# CAN.net
KiCad netlist of a schematic drawn in EAGLE
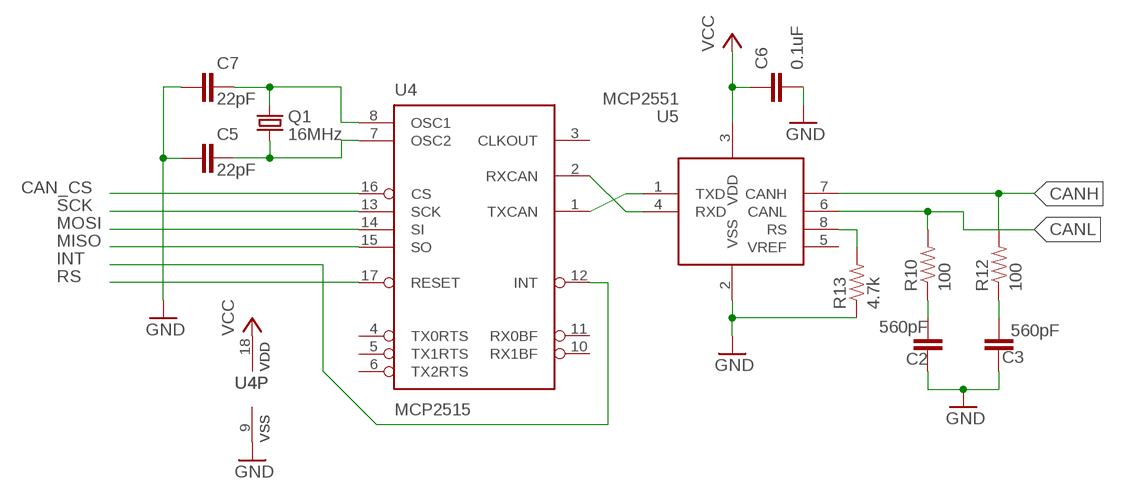
[diagram p0: schematic, sheet 1]

(export (version "E")
  (design (tool "Eeschema 10.0.6"))
  (components
    (comp (ref "C2")
      (value "560pF")
      (footprint "eagle-import:0603-CAP")
      (libsource (lib "eagle-import") (part "CAP0603-CAP"))
    )
    (comp (ref "C3")
      (value "560pF")
      (footprint "eagle-import:0603-CAP")
      (libsource (lib "eagle-import") (part "CAP0603-CAP"))
    )
    (comp (ref "C5")
      (value "22pF")
      (footprint "eagle-import:0603-CAP")
      (libsource (lib "eagle-import") (part "CAP0603-CAP"))
    )
    (comp (ref "C6")
      (value "0.1uF")
      (footprint "eagle-import:0603-CAP")
      (libsource (lib "eagle-import") (part "CAP0603-CAP"))
    )
    (comp (ref "C7")
      (value "22pF")
      (footprint "eagle-import:0603-CAP")
      (libsource (lib "eagle-import") (part "CAP0603-CAP"))
    )
    (comp (ref "Q1")
      (value "16MHz")
      (footprint "eagle-import:CRYSTAL-SMD-5X3")
      (libsource (lib "eagle-import") (part "CRYSTAL5X3"))
    )
    (comp (ref "R10")
      (value "100")
      (footprint "eagle-import:0603-RES")
      (libsource (lib "eagle-import") (part "RESISTOR0603-RES"))
    )
    (comp (ref "R12")
      (value "100")
      (footprint "eagle-import:0603-RES")
      (libsource (lib "eagle-import") (part "RESISTOR0603-RES"))
    )
    (comp (ref "R13")
      (value "4.7k")
      (footprint "eagle-import:0603-RES")
      (libsource (lib "eagle-import") (part "RESISTOR0603-RES"))
    )
    (comp (ref "U4")
      (value "MCP2515")
      (footprint "eagle-import:SO-18W")
      (libsource (lib "eagle-import") (part "MCP2510SO"))
    )
    (comp (ref "U5")
      (value "MCP2551")
      (footprint "eagle-import:SO-08M")
      (libsource (lib "eagle-import") (part "MCP2551"))
    )
  )
  (nets
    (net (code "1") (name "/CAN_CS") (class "Default")
      (node (ref "U4") (pin "16") (pinfunction "CS_16") (pintype "input"))
    )
    (net (code "2") (name "/INT") (class "Default")
      (node (ref "U4") (pin "12") (pinfunction "INT_12") (pintype "output"))
    )
    (net (code "3") (name "/MISO") (class "Default")
      (node (ref "U4") (pin "15") (pinfunction "SO_15") (pintype "output"))
    )
    (net (code "4") (name "/MOSI") (class "Default")
      (node (ref "U4") (pin "14") (pinfunction "SI_14") (pintype "input"))
    )
    (net (code "5") (name "/RS") (class "Default")
      (node (ref "U4") (pin "17") (pinfunction "RESET_17") (pintype "input"))
    )
    (net (code "6") (name "/SCK") (class "Default")
      (node (ref "U4") (pin "13") (pinfunction "SCK_13") (pintype "input"))
    )
    (net (code "7") (name "CANH") (class "Default")
      (node (ref "R12") (pin "2") (pinfunction "2_2") (pintype "passive"))
      (node (ref "U5") (pin "7") (pinfunction "CANH_7") (pintype "bidirectional"))
    )
    (net (code "8") (name "CANL") (class "Default")
      (node (ref "R10") (pin "2") (pinfunction "2_2") (pintype "passive"))
      (node (ref "U5") (pin "6") (pinfunction "CANL_6") (pintype "bidirectional"))
    )
    (net (code "9") (name "GND") (class "Default")
      (node (ref "C2") (pin "1") (pinfunction "1_1") (pintype "passive"))
      (node (ref "C3") (pin "1") (pinfunction "1_1") (pintype "passive"))
      (node (ref "C5") (pin "1") (pinfunction "1_1") (pintype "passive"))
      (node (ref "C6") (pin "1") (pinfunction "1_1") (pintype "passive"))
      (node (ref "C7") (pin "1") (pinfunction "1_1") (pintype "passive"))
      (node (ref "R13") (pin "1") (pinfunction "1_1") (pintype "passive"))
      (node (ref "U4") (pin "9") (pinfunction "VSS_9") (pintype "power_in"))
      (node (ref "U5") (pin "2") (pinfunction "VSS_2") (pintype "power_in"))
    )
    (net (code "10") (name "Net-(C2-Pad2)") (class "Default")
      (node (ref "C2") (pin "2") (pinfunction "2_2") (pintype "passive"))
      (node (ref "R10") (pin "1") (pinfunction "1_1") (pintype "passive"))
    )
    (net (code "11") (name "Net-(C3-Pad2)") (class "Default")
      (node (ref "C3") (pin "2") (pinfunction "2_2") (pintype "passive"))
      (node (ref "R12") (pin "1") (pinfunction "1_1") (pintype "passive"))
    )
    (net (code "12") (name "Net-(Q1-2)") (class "Default")
      (node (ref "C7") (pin "2") (pinfunction "2_2") (pintype "passive"))
      (node (ref "Q1") (pin "3") (pinfunction "2_3") (pintype "passive"))
      (node (ref "U4") (pin "8") (pinfunction "OSC1_8") (pintype "input"))
    )
    (net (code "13") (name "Net-(U4A-OSC2)") (class "Default")
      (node (ref "C5") (pin "2") (pinfunction "2_2") (pintype "passive"))
      (node (ref "Q1") (pin "1") (pinfunction "1_1") (pintype "passive"))
      (node (ref "U4") (pin "7") (pinfunction "OSC2_7") (pintype "output"))
    )
    (net (code "14") (name "Net-(U4A-RXCAN)") (class "Default")
      (node (ref "U4") (pin "2") (pinfunction "RXCAN_2") (pintype "input"))
      (node (ref "U5") (pin "4") (pinfunction "RXD_4") (pintype "bidirectional"))
    )
    (net (code "15") (name "Net-(U4A-TXCAN)") (class "Default")
      (node (ref "U4") (pin "1") (pinfunction "TXCAN_1") (pintype "output"))
      (node (ref "U5") (pin "1") (pinfunction "TXD_1") (pintype "bidirectional"))
    )
    (net (code "16") (name "Net-(U5-RS)") (class "Default")
      (node (ref "R13") (pin "2") (pinfunction "2_2") (pintype "passive"))
      (node (ref "U5") (pin "8") (pinfunction "RS_8") (pintype "bidirectional"))
    )
    (net (code "17") (name "VCC") (class "Default")
      (node (ref "C6") (pin "2") (pinfunction "2_2") (pintype "passive"))
      (node (ref "U4") (pin "18") (pinfunction "VDD_18") (pintype "power_in"))
      (node (ref "U5") (pin "3") (pinfunction "VDD_3") (pintype "power_in"))
    )
    (net (code "18") (name "unconnected-(U4A-CLKOUT-Pad3)") (class "Default")
      (node (ref "U4") (pin "3") (pinfunction "CLKOUT_3") (pintype "output"))
    )
    (net (code "19") (name "unconnected-(U4A-RX0BF-Pad11)") (class "Default")
      (node (ref "U4") (pin "11") (pinfunction "RX0BF_11") (pintype "output"))
    )
    (net (code "20") (name "unconnected-(U4A-RX1BF-Pad10)") (class "Default")
      (node (ref "U4") (pin "10") (pinfunction "RX1BF_10") (pintype "output"))
    )
    (net (code "21") (name "unconnected-(U4A-TX0RTS-Pad4)") (class "Default")
      (node (ref "U4") (pin "4") (pinfunction "TX0RTS_4") (pintype "input"))
    )
    (net (code "22") (name "unconnected-(U4A-TX1RTS-Pad5)") (class "Default")
      (node (ref "U4") (pin "5") (pinfunction "TX1RTS_5") (pintype "input"))
    )
    (net (code "23") (name "unconnected-(U4A-TX2RTS-Pad6)") (class "Default")
      (node (ref "U4") (pin "6") (pinfunction "TX2RTS_6") (pintype "input"))
    )
    (net (code "24") (name "unconnected-(U5-VREF-Pad5)") (class "Default")
      (node (ref "U5") (pin "5") (pinfunction "VREF_5") (pintype "bidirectional"))
    )
  )
)
